# ioshield.net
KiCad netlist of a schematic drawn in EAGLE
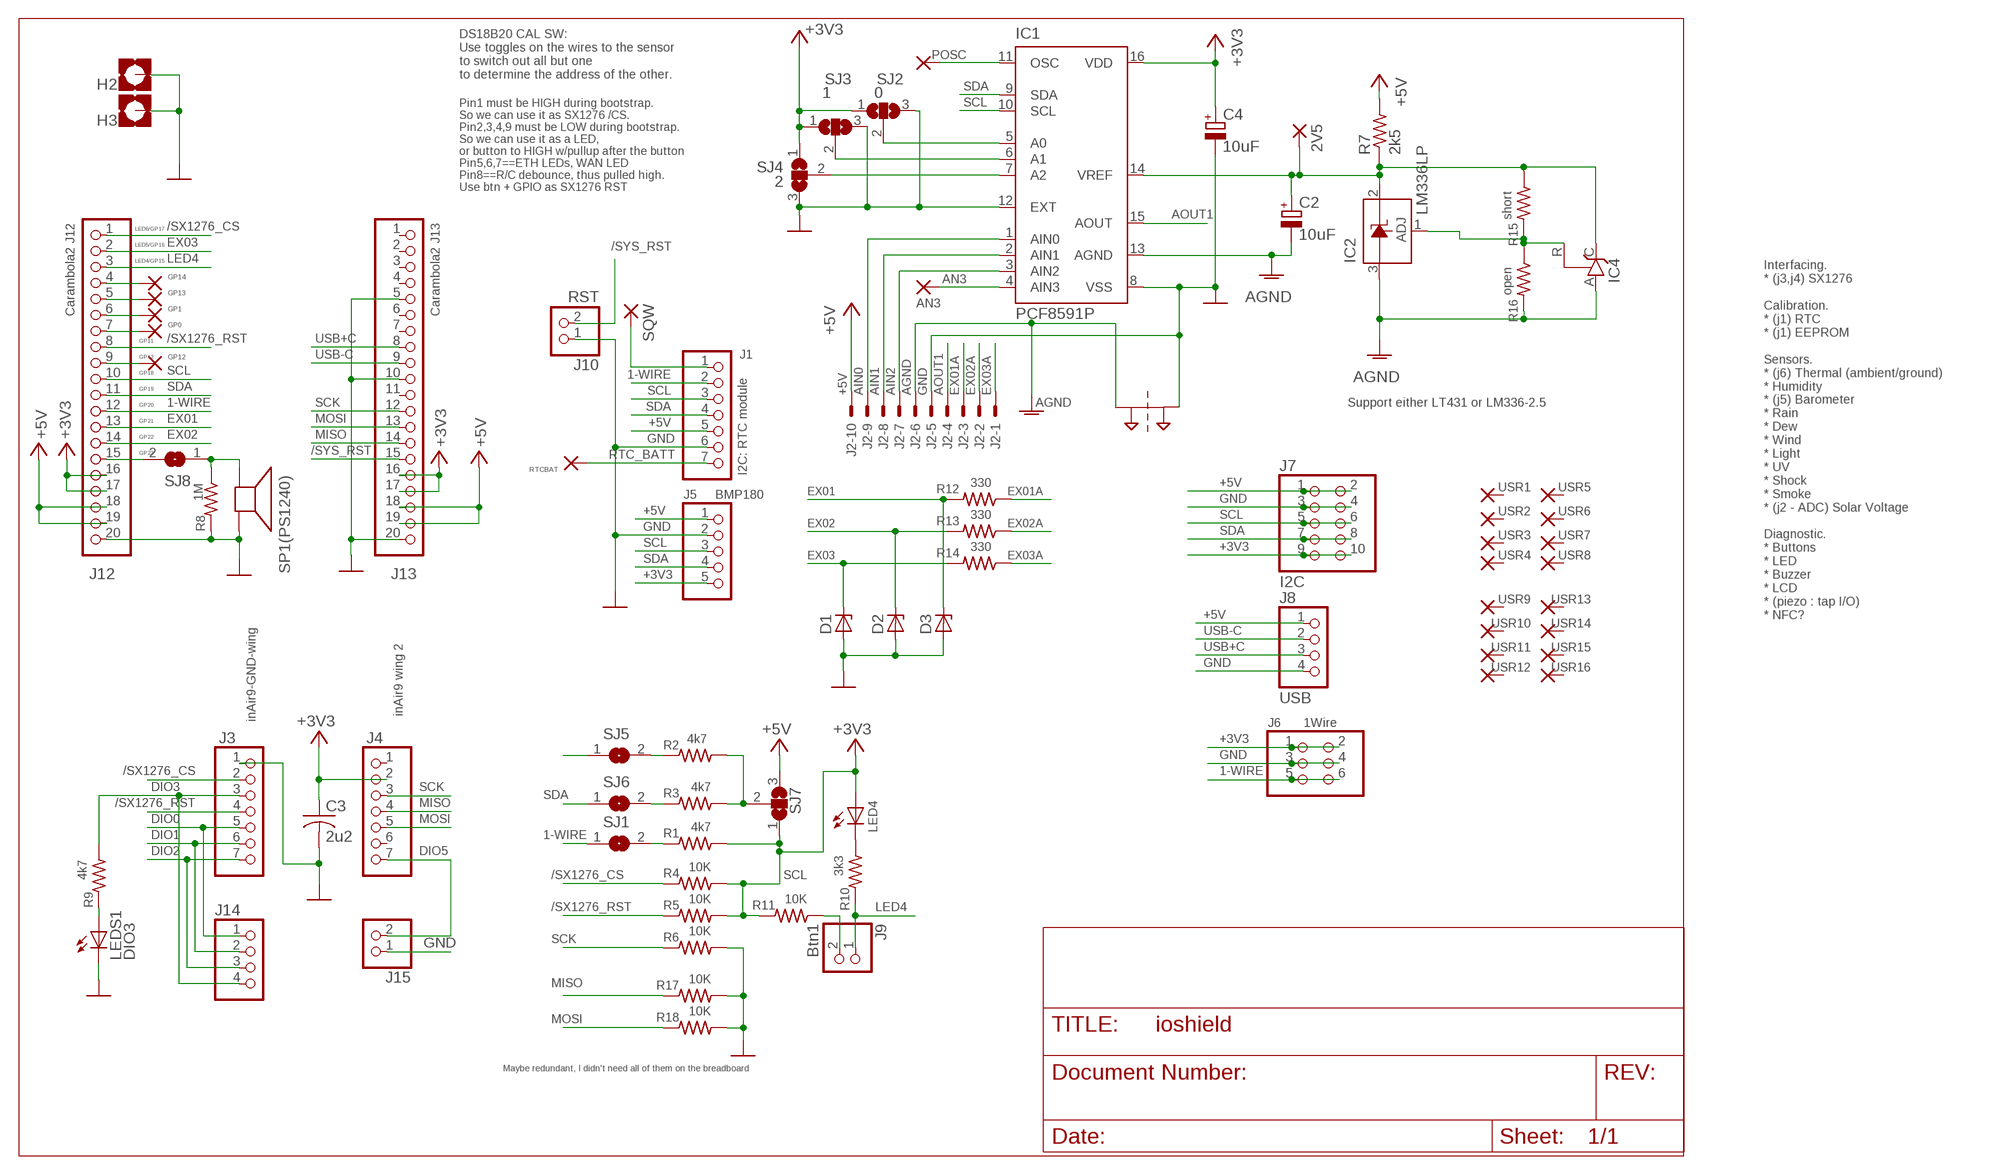
[diagram p0: schematic, sheet 1]

(export (version "E")
  (design (tool "Eeschema 10.0.6"))
  (components
    (comp (ref "2V5")
      (value "2,54/0,8")
      (footprint "eagle-import:2,54_0,8")
      (libsource (lib "eagle-import") (part "2,54/0,8"))
    )
    (comp (ref "AN3")
      (value "AN3")
      (footprint "eagle-import:2,54_0,8")
      (libsource (lib "eagle-import") (part "2,54/0,8"))
    )
    (comp (ref "C2")
      (value "10uF")
      (footprint "eagle-import:E2,5-5")
      (libsource (lib "eagle-import") (part "CPOL-EUE2.5-5"))
    )
    (comp (ref "C3")
      (value "2u2")
      (footprint "eagle-import:C1206")
      (libsource (lib "eagle-import") (part "C-USC1206"))
    )
    (comp (ref "C4")
      (value "10uF")
      (footprint "eagle-import:E2,5-5")
      (libsource (lib "eagle-import") (part "CPOL-EUE2.5-5"))
    )
    (comp (ref "D1")
      (value "ZENER-DIODEZD-2.5")
      (footprint "eagle-import:ZDIO-2.5")
      (libsource (lib "eagle-import") (part "ZENER-DIODEZD-2.5"))
    )
    (comp (ref "D2")
      (value "ZENER-DIODEZD-2.5")
      (footprint "eagle-import:ZDIO-2.5")
      (libsource (lib "eagle-import") (part "ZENER-DIODEZD-2.5"))
    )
    (comp (ref "D3")
      (value "ZENER-DIODEZD-2.5")
      (footprint "eagle-import:ZDIO-2.5")
      (libsource (lib "eagle-import") (part "ZENER-DIODEZD-2.5"))
    )
    (comp (ref "GP0")
      (value "2,54/0,8")
      (footprint "eagle-import:2,54_0,8")
      (libsource (lib "eagle-import") (part "2,54/0,8"))
    )
    (comp (ref "GP1")
      (value "2,54/0,8")
      (footprint "eagle-import:2,54_0,8")
      (libsource (lib "eagle-import") (part "2,54/0,8"))
    )
    (comp (ref "GP12")
      (value "2,54/0,8")
      (footprint "eagle-import:2,54_0,8")
      (libsource (lib "eagle-import") (part "2,54/0,8"))
    )
    (comp (ref "GP13")
      (value "2,54/0,8")
      (footprint "eagle-import:2,54_0,8")
      (libsource (lib "eagle-import") (part "2,54/0,8"))
    )
    (comp (ref "GP14")
      (value "2,54/0,8")
      (footprint "eagle-import:2,54_0,8")
      (libsource (lib "eagle-import") (part "2,54/0,8"))
    )
    (comp (ref "H2")
      (value "MOUNT-PAD-SQUARE3.2")
      (footprint "eagle-import:3,2-PAD-SQUARE")
      (libsource (lib "eagle-import") (part "MOUNT-PAD-SQUARE3.2"))
    )
    (comp (ref "H3")
      (value "MOUNT-PAD-SQUARE3.2")
      (footprint "eagle-import:3,2-PAD-SQUARE")
      (libsource (lib "eagle-import") (part "MOUNT-PAD-SQUARE3.2"))
    )
    (comp (ref "IC1")
      (value "PCF8591P")
      (footprint "eagle-import:DIL16")
      (fields (field (name "MF") "FARNELL"))
      (libsource (lib "eagle-import") (part "PCF8591P"))
    )
    (comp (ref "IC2")
      (value "LM336LP")
      (footprint "eagle-import:TO92")
      (libsource (lib "eagle-import") (part "LM336LP"))
    )
    (comp (ref "IC4")
      (value "TL431CLP")
      (footprint "eagle-import:TO92-CLP")
      (libsource (lib "eagle-import") (part "TL431CLP"))
    )
    (comp (ref "J1")
      (value "I2C: RTC module")
      (footprint "eagle-import:1X07")
      (libsource (lib "eagle-import") (part "PINHD-1X7"))
    )
    (comp (ref "J2")
      (value "22-23-2101")
      (footprint "eagle-import:22-23-2101")
      (fields (field (name "MF") "MOLEX") (field (name "MPN") "Screw Terminal"))
      (libsource (lib "eagle-import") (part "22-23-2101"))
    )
    (comp (ref "J3")
      (value "inAir9-GND-wing")
      (footprint "eagle-import:1X07")
      (libsource (lib "eagle-import") (part "PINHD-1X7"))
    )
    (comp (ref "J4")
      (value "inAir9 wing 2")
      (footprint "eagle-import:1X07")
      (libsource (lib "eagle-import") (part "PINHD-1X7"))
    )
    (comp (ref "J5")
      (value "BMP180")
      (footprint "eagle-import:1X05")
      (libsource (lib "eagle-import") (part "PINHD-1X5"))
    )
    (comp (ref "J6")
      (value "1Wire")
      (footprint "eagle-import:2X03")
      (libsource (lib "eagle-import") (part "PINHD-2X3"))
    )
    (comp (ref "J7")
      (value "I2C")
      (footprint "eagle-import:2X05")
      (libsource (lib "eagle-import") (part "PINHD-2X5"))
    )
    (comp (ref "J8")
      (value "USB")
      (footprint "eagle-import:1X04")
      (libsource (lib "eagle-import") (part "PINHD-1X4"))
    )
    (comp (ref "J9")
      (value "Btn1")
      (footprint "eagle-import:1X02")
      (libsource (lib "eagle-import") (part "PINHD-1X2"))
    )
    (comp (ref "J10")
      (value "RST")
      (footprint "eagle-import:1X02")
      (libsource (lib "eagle-import") (part "PINHD-1X2"))
    )
    (comp (ref "J12")
      (value "Carambola2 J12")
      (footprint "eagle-import:1X20")
      (libsource (lib "eagle-import") (part "PINHD-1X20"))
    )
    (comp (ref "J13")
      (value "Carambola2 J13")
      (footprint "eagle-import:1X20")
      (libsource (lib "eagle-import") (part "PINHD-1X20"))
    )
    (comp (ref "J14")
      (value "PINHD-1X4")
      (footprint "eagle-import:1X04")
      (libsource (lib "eagle-import") (part "PINHD-1X4"))
    )
    (comp (ref "J15")
      (value "PINHD-1X2")
      (footprint "eagle-import:1X02")
      (libsource (lib "eagle-import") (part "PINHD-1X2"))
    )
    (comp (ref "LED4")
      (value "LED3MM")
      (footprint "eagle-import:LED3MM")
      (libsource (lib "eagle-import") (part "LED3MM"))
    )
    (comp (ref "LEDS1")
      (value "DIO3")
      (footprint "eagle-import:LED3MM")
      (libsource (lib "eagle-import") (part "LED3MM"))
    )
    (comp (ref "POSC")
      (value "2,54/0,8")
      (footprint "eagle-import:2,54_0,8")
      (libsource (lib "eagle-import") (part "2,54/0,8"))
    )
    (comp (ref "PT1")
      (value "2PT_GND_TIE")
      (footprint "eagle-import:2PT_GND_TIE")
      (libsource (lib "eagle-import") (part "2PT_GND_TIE"))
    )
    (comp (ref "R1")
      (value "4k7")
      (footprint "eagle-import:M1206")
      (libsource (lib "eagle-import") (part "R-US_M1206"))
    )
    (comp (ref "R2")
      (value "4k7")
      (footprint "eagle-import:M1206")
      (libsource (lib "eagle-import") (part "R-US_M1206"))
    )
    (comp (ref "R3")
      (value "4k7")
      (footprint "eagle-import:M1206")
      (libsource (lib "eagle-import") (part "R-US_M1206"))
    )
    (comp (ref "R4")
      (value "10K")
      (footprint "eagle-import:M1206")
      (libsource (lib "eagle-import") (part "R-US_M1206"))
    )
    (comp (ref "R5")
      (value "10K")
      (footprint "eagle-import:M1206")
      (libsource (lib "eagle-import") (part "R-US_M1206"))
    )
    (comp (ref "R6")
      (value "10K")
      (footprint "eagle-import:M1206")
      (libsource (lib "eagle-import") (part "R-US_M1206"))
    )
    (comp (ref "R7")
      (value "2k5")
      (footprint "eagle-import:M1206")
      (libsource (lib "eagle-import") (part "R-US_M1206"))
    )
    (comp (ref "R8")
      (value "1M")
      (footprint "eagle-import:M1206")
      (libsource (lib "eagle-import") (part "R-US_M1206"))
    )
    (comp (ref "R9")
      (value "4k7")
      (footprint "eagle-import:M1206")
      (libsource (lib "eagle-import") (part "R-US_M1206"))
    )
    (comp (ref "R10")
      (value "3k3")
      (footprint "eagle-import:M1206")
      (libsource (lib "eagle-import") (part "R-US_M1206"))
    )
    (comp (ref "R11")
      (value "10K")
      (footprint "eagle-import:M1206")
      (libsource (lib "eagle-import") (part "R-US_M1206"))
    )
    (comp (ref "R12")
      (value "330")
      (footprint "eagle-import:M1206")
      (libsource (lib "eagle-import") (part "R-US_M1206"))
    )
    (comp (ref "R13")
      (value "330")
      (footprint "eagle-import:M1206")
      (libsource (lib "eagle-import") (part "R-US_M1206"))
    )
    (comp (ref "R14")
      (value "330")
      (footprint "eagle-import:M1206")
      (libsource (lib "eagle-import") (part "R-US_M1206"))
    )
    (comp (ref "R15")
      (value "short")
      (footprint "eagle-import:M1206")
      (libsource (lib "eagle-import") (part "R-US_M1206"))
    )
    (comp (ref "R16")
      (value "open")
      (footprint "eagle-import:M1206")
      (libsource (lib "eagle-import") (part "R-US_M1206"))
    )
    (comp (ref "R17")
      (value "10K")
      (footprint "eagle-import:M1206")
      (libsource (lib "eagle-import") (part "R-US_M1206"))
    )
    (comp (ref "R18")
      (value "10K")
      (footprint "eagle-import:M1206")
      (libsource (lib "eagle-import") (part "R-US_M1206"))
    )
    (comp (ref "RTCBAT")
      (value "2,54/0,8")
      (footprint "eagle-import:2,54_0,8")
      (libsource (lib "eagle-import") (part "2,54/0,8"))
    )
    (comp (ref "SJ1") (value "SJ") (footprint "eagle-import:SJ") (libsource (lib "eagle-import") (part "SJ")))
    (comp (ref "SJ2")
      (value "0")
      (footprint "eagle-import:SJ_2")
      (libsource (lib "eagle-import") (part "SJ2W"))
    )
    (comp (ref "SJ3")
      (value "1")
      (footprint "eagle-import:SJ_2")
      (libsource (lib "eagle-import") (part "SJ2W"))
    )
    (comp (ref "SJ4")
      (value "2")
      (footprint "eagle-import:SJ_2")
      (libsource (lib "eagle-import") (part "SJ2W"))
    )
    (comp (ref "SJ5") (value "SJ") (footprint "eagle-import:SJ") (libsource (lib "eagle-import") (part "SJ")))
    (comp (ref "SJ6") (value "SJ") (footprint "eagle-import:SJ") (libsource (lib "eagle-import") (part "SJ")))
    (comp (ref "SJ7")
      (value "SJ2W")
      (footprint "eagle-import:SJ_2")
      (libsource (lib "eagle-import") (part "SJ2W"))
    )
    (comp (ref "SJ8") (value "SJ") (footprint "eagle-import:SJ") (libsource (lib "eagle-import") (part "SJ")))
    (comp (ref "SP1(PS1240)")
      (value "SPEAKER/AL11P")
      (footprint "eagle-import:AL11P")
      (libsource (lib "eagle-import") (part "SPEAKER/AL11P"))
    )
    (comp (ref "SQW")
      (value "2,54/0,8")
      (footprint "eagle-import:2,54_0,8")
      (libsource (lib "eagle-import") (part "2,54/0,8"))
    )
    (comp (ref "USR1")
      (value "1,6/0,8")
      (footprint "eagle-import:1,6_0,8")
      (libsource (lib "eagle-import") (part "1,6/0,8"))
    )
    (comp (ref "USR2")
      (value "1,6/0,8")
      (footprint "eagle-import:1,6_0,8")
      (libsource (lib "eagle-import") (part "1,6/0,8"))
    )
    (comp (ref "USR3")
      (value "1,6/0,8")
      (footprint "eagle-import:1,6_0,8")
      (libsource (lib "eagle-import") (part "1,6/0,8"))
    )
    (comp (ref "USR4")
      (value "1,6/0,8")
      (footprint "eagle-import:1,6_0,8")
      (libsource (lib "eagle-import") (part "1,6/0,8"))
    )
    (comp (ref "USR5")
      (value "1,6/0,8")
      (footprint "eagle-import:1,6_0,8")
      (libsource (lib "eagle-import") (part "1,6/0,8"))
    )
    (comp (ref "USR6")
      (value "1,6/0,8")
      (footprint "eagle-import:1,6_0,8")
      (libsource (lib "eagle-import") (part "1,6/0,8"))
    )
    (comp (ref "USR7")
      (value "1,6/0,8")
      (footprint "eagle-import:1,6_0,8")
      (libsource (lib "eagle-import") (part "1,6/0,8"))
    )
    (comp (ref "USR8")
      (value "1,6/0,8")
      (footprint "eagle-import:1,6_0,8")
      (libsource (lib "eagle-import") (part "1,6/0,8"))
    )
    (comp (ref "USR9")
      (value "1,6/0,8")
      (footprint "eagle-import:1,6_0,8")
      (libsource (lib "eagle-import") (part "1,6/0,8"))
    )
    (comp (ref "USR10")
      (value "1,6/0,8")
      (footprint "eagle-import:1,6_0,8")
      (libsource (lib "eagle-import") (part "1,6/0,8"))
    )
    (comp (ref "USR11")
      (value "1,6/0,8")
      (footprint "eagle-import:1,6_0,8")
      (libsource (lib "eagle-import") (part "1,6/0,8"))
    )
    (comp (ref "USR12")
      (value "1,6/0,8")
      (footprint "eagle-import:1,6_0,8")
      (libsource (lib "eagle-import") (part "1,6/0,8"))
    )
    (comp (ref "USR13")
      (value "1,6/0,8")
      (footprint "eagle-import:1,6_0,8")
      (libsource (lib "eagle-import") (part "1,6/0,8"))
    )
    (comp (ref "USR14")
      (value "1,6/0,8")
      (footprint "eagle-import:1,6_0,8")
      (libsource (lib "eagle-import") (part "1,6/0,8"))
    )
    (comp (ref "USR15")
      (value "1,6/0,8")
      (footprint "eagle-import:1,6_0,8")
      (libsource (lib "eagle-import") (part "1,6/0,8"))
    )
    (comp (ref "USR16")
      (value "1,6/0,8")
      (footprint "eagle-import:1,6_0,8")
      (libsource (lib "eagle-import") (part "1,6/0,8"))
    )
  )
  (nets
    (net (code "1") (name "+3V3") (class "Default")
      (node (ref "C3") (pin "1") (pinfunction "1_1") (pintype "passive"))
      (node (ref "C4") (pin "+") (pinfunction "+_+") (pintype "passive"))
      (node (ref "IC1") (pin "16") (pinfunction "VDD_16") (pintype "power_in"))
      (node (ref "J12") (pin "16") (pinfunction "16_16") (pintype "passive"))
      (node (ref "J12") (pin "17") (pinfunction "17_17") (pintype "passive"))
      (node (ref "J13") (pin "16") (pinfunction "16_16") (pintype "passive"))
      (node (ref "J13") (pin "17") (pinfunction "17_17") (pintype "passive"))
      (node (ref "J4") (pin "2") (pinfunction "2_2") (pintype "passive"))
      (node (ref "J5") (pin "5") (pinfunction "5_5") (pintype "passive"))
      (node (ref "J6") (pin "1") (pinfunction "1_1") (pintype "passive"))
      (node (ref "J6") (pin "2") (pinfunction "2_2") (pintype "passive"))
      (node (ref "J7") (pin "10") (pinfunction "10_10") (pintype "passive"))
      (node (ref "J7") (pin "9") (pinfunction "9_9") (pintype "passive"))
      (node (ref "LED4") (pin "A") (pinfunction "A_A") (pintype "passive"))
      (node (ref "R1") (pin "1") (pinfunction "1_1") (pintype "passive"))
      (node (ref "R11") (pin "2") (pinfunction "2_2") (pintype "passive"))
      (node (ref "R4") (pin "1") (pinfunction "1_1") (pintype "passive"))
      (node (ref "R5") (pin "1") (pinfunction "1_1") (pintype "passive"))
      (node (ref "SJ2") (pin "1") (pinfunction "1_1") (pintype "passive"))
      (node (ref "SJ3") (pin "1") (pinfunction "1_1") (pintype "passive"))
      (node (ref "SJ4") (pin "1") (pinfunction "1_1") (pintype "passive"))
      (node (ref "SJ7") (pin "1") (pinfunction "1_1") (pintype "passive"))
    )
    (net (code "2") (name "+5V") (class "Default")
      (node (ref "J1") (pin "5") (pinfunction "5_5") (pintype "passive"))
      (node (ref "J12") (pin "18") (pinfunction "18_18") (pintype "passive"))
      (node (ref "J12") (pin "19") (pinfunction "19_19") (pintype "passive"))
      (node (ref "J13") (pin "18") (pinfunction "18_18") (pintype "passive"))
      (node (ref "J13") (pin "19") (pinfunction "19_19") (pintype "passive"))
      (node (ref "J2") (pin "10") (pinfunction "S_10") (pintype "passive"))
      (node (ref "J5") (pin "1") (pinfunction "1_1") (pintype "passive"))
      (node (ref "J7") (pin "1") (pinfunction "1_1") (pintype "passive"))
      (node (ref "J7") (pin "2") (pinfunction "2_2") (pintype "passive"))
      (node (ref "J8") (pin "1") (pinfunction "1_1") (pintype "passive"))
      (node (ref "R7") (pin "2") (pinfunction "2_2") (pintype "passive"))
      (node (ref "SJ7") (pin "3") (pinfunction "3_3") (pintype "passive"))
    )
    (net (code "3") (name "/1-WIRE") (class "Default")
      (node (ref "J1") (pin "2") (pinfunction "2_2") (pintype "passive"))
      (node (ref "J12") (pin "12") (pinfunction "12_12") (pintype "passive"))
      (node (ref "J6") (pin "5") (pinfunction "5_5") (pintype "passive"))
      (node (ref "J6") (pin "6") (pinfunction "6_6") (pintype "passive"))
      (node (ref "SJ1") (pin "1") (pinfunction "1_1") (pintype "passive"))
    )
    (net (code "4") (name "/AIN0") (class "Default")
      (node (ref "IC1") (pin "1") (pinfunction "AIN0_1") (pintype "input"))
      (node (ref "J2") (pin "9") (pinfunction "S_9") (pintype "passive"))
    )
    (net (code "5") (name "/AIN1") (class "Default")
      (node (ref "IC1") (pin "2") (pinfunction "AIN1_2") (pintype "input"))
      (node (ref "J2") (pin "8") (pinfunction "S_8") (pintype "passive"))
    )
    (net (code "6") (name "/AIN2") (class "Default")
      (node (ref "IC1") (pin "3") (pinfunction "AIN2_3") (pintype "input"))
      (node (ref "J2") (pin "7") (pinfunction "S_7") (pintype "passive"))
    )
    (net (code "7") (name "/AOUT1") (class "Default")
      (node (ref "IC1") (pin "15") (pinfunction "AOUT_15") (pintype "output"))
      (node (ref "J2") (pin "4") (pinfunction "S_4") (pintype "passive"))
    )
    (net (code "8") (name "/DIO0") (class "Default")
      (node (ref "J14") (pin "1") (pinfunction "1_1") (pintype "passive"))
      (node (ref "J3") (pin "5") (pinfunction "5_5") (pintype "passive"))
    )
    (net (code "9") (name "/DIO1") (class "Default")
      (node (ref "J14") (pin "2") (pinfunction "2_2") (pintype "passive"))
      (node (ref "J3") (pin "6") (pinfunction "6_6") (pintype "passive"))
    )
    (net (code "10") (name "/DIO2") (class "Default")
      (node (ref "J14") (pin "3") (pinfunction "3_3") (pintype "passive"))
      (node (ref "J3") (pin "7") (pinfunction "7_7") (pintype "passive"))
    )
    (net (code "11") (name "/DIO3") (class "Default")
      (node (ref "J14") (pin "4") (pinfunction "4_4") (pintype "passive"))
      (node (ref "J3") (pin "3") (pinfunction "3_3") (pintype "passive"))
      (node (ref "R9") (pin "1") (pinfunction "1_1") (pintype "passive"))
    )
    (net (code "12") (name "/DIO5") (class "Default")
      (node (ref "J15") (pin "2") (pinfunction "2_2") (pintype "passive"))
      (node (ref "J4") (pin "7") (pinfunction "7_7") (pintype "passive"))
    )
    (net (code "13") (name "/EX01") (class "Default")
      (node (ref "D3") (pin "C") (pinfunction "C_C") (pintype "passive"))
      (node (ref "J12") (pin "13") (pinfunction "13_13") (pintype "passive"))
      (node (ref "R12") (pin "2") (pinfunction "2_2") (pintype "passive"))
    )
    (net (code "14") (name "/EX01A") (class "Default")
      (node (ref "J2") (pin "3") (pinfunction "S_3") (pintype "passive"))
      (node (ref "R12") (pin "1") (pinfunction "1_1") (pintype "passive"))
    )
    (net (code "15") (name "/EX02") (class "Default")
      (node (ref "D2") (pin "C") (pinfunction "C_C") (pintype "passive"))
      (node (ref "J12") (pin "14") (pinfunction "14_14") (pintype "passive"))
      (node (ref "R13") (pin "2") (pinfunction "2_2") (pintype "passive"))
    )
    (net (code "16") (name "/EX02A") (class "Default")
      (node (ref "J2") (pin "2") (pinfunction "S_2") (pintype "passive"))
      (node (ref "R13") (pin "1") (pinfunction "1_1") (pintype "passive"))
    )
    (net (code "17") (name "/EX03") (class "Default")
      (node (ref "D1") (pin "C") (pinfunction "C_C") (pintype "passive"))
      (node (ref "J12") (pin "2") (pinfunction "2_2") (pintype "passive"))
      (node (ref "R14") (pin "2") (pinfunction "2_2") (pintype "passive"))
    )
    (net (code "18") (name "/EX03A") (class "Default")
      (node (ref "J2") (pin "1") (pinfunction "S_1") (pintype "passive"))
      (node (ref "R14") (pin "1") (pinfunction "1_1") (pintype "passive"))
    )
    (net (code "19") (name "/LED4") (class "Default")
      (node (ref "J12") (pin "3") (pinfunction "3_3") (pintype "passive"))
      (node (ref "J9") (pin "1") (pinfunction "1_1") (pintype "passive"))
      (node (ref "R10") (pin "2") (pinfunction "2_2") (pintype "passive"))
    )
    (net (code "20") (name "/MISO") (class "Default")
      (node (ref "J13") (pin "14") (pinfunction "14_14") (pintype "passive"))
      (node (ref "J4") (pin "4") (pinfunction "4_4") (pintype "passive"))
      (node (ref "R17") (pin "2") (pinfunction "2_2") (pintype "passive"))
    )
    (net (code "21") (name "/MOSI") (class "Default")
      (node (ref "J13") (pin "13") (pinfunction "13_13") (pintype "passive"))
      (node (ref "J4") (pin "5") (pinfunction "5_5") (pintype "passive"))
      (node (ref "R18") (pin "2") (pinfunction "2_2") (pintype "passive"))
    )
    (net (code "22") (name "/RTC_BATT") (class "Default")
      (node (ref "J1") (pin "7") (pinfunction "7_7") (pintype "passive"))
      (node (ref "RTCBAT") (pin "1") (pinfunction "P_1") (pintype "passive"))
    )
    (net (code "23") (name "/SCK") (class "Default")
      (node (ref "J13") (pin "12") (pinfunction "12_12") (pintype "passive"))
      (node (ref "J4") (pin "3") (pinfunction "3_3") (pintype "passive"))
      (node (ref "R6") (pin "2") (pinfunction "2_2") (pintype "passive"))
    )
    (net (code "24") (name "/SCL") (class "Default")
      (node (ref "IC1") (pin "10") (pinfunction "SCL_10") (pintype "input"))
      (node (ref "J1") (pin "3") (pinfunction "3_3") (pintype "passive"))
      (node (ref "J12") (pin "10") (pinfunction "10_10") (pintype "passive"))
      (node (ref "J5") (pin "3") (pinfunction "3_3") (pintype "passive"))
      (node (ref "J7") (pin "5") (pinfunction "5_5") (pintype "passive"))
      (node (ref "J7") (pin "6") (pinfunction "6_6") (pintype "passive"))
      (node (ref "SJ5") (pin "1") (pinfunction "1_1") (pintype "passive"))
    )
    (net (code "25") (name "/SDA") (class "Default")
      (node (ref "IC1") (pin "9") (pinfunction "SDA_9") (pintype "bidirectional"))
      (node (ref "J1") (pin "4") (pinfunction "4_4") (pintype "passive"))
      (node (ref "J12") (pin "11") (pinfunction "11_11") (pintype "passive"))
      (node (ref "J5") (pin "4") (pinfunction "4_4") (pintype "passive"))
      (node (ref "J7") (pin "7") (pinfunction "7_7") (pintype "passive"))
      (node (ref "J7") (pin "8") (pinfunction "8_8") (pintype "passive"))
      (node (ref "SJ6") (pin "1") (pinfunction "1_1") (pintype "passive"))
    )
    (net (code "26") (name "/USB+C") (class "Default")
      (node (ref "J13") (pin "8") (pinfunction "8_8") (pintype "passive"))
      (node (ref "J8") (pin "3") (pinfunction "3_3") (pintype "passive"))
    )
    (net (code "27") (name "/USB-C") (class "Default")
      (node (ref "J13") (pin "9") (pinfunction "9_9") (pintype "passive"))
      (node (ref "J8") (pin "2") (pinfunction "2_2") (pintype "passive"))
    )
    (net (code "28") (name "/{slash}SX1276_CS") (class "Default")
      (node (ref "J12") (pin "1") (pinfunction "1_1") (pintype "passive"))
      (node (ref "J3") (pin "2") (pinfunction "2_2") (pintype "passive"))
      (node (ref "R4") (pin "2") (pinfunction "2_2") (pintype "passive"))
    )
    (net (code "29") (name "/{slash}SX1276_RST") (class "Default")
      (node (ref "J12") (pin "8") (pinfunction "8_8") (pintype "passive"))
      (node (ref "J3") (pin "4") (pinfunction "4_4") (pintype "passive"))
      (node (ref "R5") (pin "2") (pinfunction "2_2") (pintype "passive"))
    )
    (net (code "30") (name "/{slash}SYS_RST") (class "Default")
      (node (ref "J10") (pin "2") (pinfunction "2_2") (pintype "passive"))
      (node (ref "J13") (pin "15") (pinfunction "15_15") (pintype "passive"))
    )
    (net (code "31") (name "AGND") (class "Default")
      (node (ref "C2") (pin "-") (pinfunction "-_-") (pintype "passive"))
      (node (ref "IC1") (pin "13") (pinfunction "AGND_13") (pintype "power_in"))
      (node (ref "IC2") (pin "3") (pinfunction "A_3") (pintype "input"))
      (node (ref "IC4") (pin "A") (pinfunction "A_A") (pintype "passive"))
      (node (ref "J2") (pin "6") (pinfunction "S_6") (pintype "passive"))
      (node (ref "PT1") (pin "P$1") (pinfunction "P$1_P$1") (pintype "bidirectional"))
      (node (ref "R16") (pin "2") (pinfunction "2_2") (pintype "passive"))
    )
    (net (code "32") (name "GND") (class "Default")
      (node (ref "C3") (pin "2") (pinfunction "2_2") (pintype "passive"))
      (node (ref "C4") (pin "-") (pinfunction "-_-") (pintype "passive"))
      (node (ref "D1") (pin "A") (pinfunction "A_A") (pintype "passive"))
      (node (ref "D2") (pin "A") (pinfunction "A_A") (pintype "passive"))
      (node (ref "D3") (pin "A") (pinfunction "A_A") (pintype "passive"))
      (node (ref "H2") (pin "B3,2") (pinfunction "MOUNT_B3,2") (pintype "passive"))
      (node (ref "H3") (pin "B3,2") (pinfunction "MOUNT_B3,2") (pintype "passive"))
      (node (ref "IC1") (pin "12") (pinfunction "EXT_12") (pintype "input"))
      (node (ref "IC1") (pin "8") (pinfunction "VSS_8") (pintype "power_in"))
      (node (ref "J1") (pin "6") (pinfunction "6_6") (pintype "passive"))
      (node (ref "J10") (pin "1") (pinfunction "1_1") (pintype "passive"))
      (node (ref "J12") (pin "20") (pinfunction "20_20") (pintype "passive"))
      (node (ref "J13") (pin "10") (pinfunction "10_10") (pintype "passive"))
      (node (ref "J13") (pin "20") (pinfunction "20_20") (pintype "passive"))
      (node (ref "J13") (pin "5") (pinfunction "5_5") (pintype "passive"))
      (node (ref "J15") (pin "1") (pinfunction "1_1") (pintype "passive"))
      (node (ref "J2") (pin "5") (pinfunction "S_5") (pintype "passive"))
      (node (ref "J3") (pin "1") (pinfunction "1_1") (pintype "passive"))
      (node (ref "J5") (pin "2") (pinfunction "2_2") (pintype "passive"))
      (node (ref "J6") (pin "3") (pinfunction "3_3") (pintype "passive"))
      (node (ref "J6") (pin "4") (pinfunction "4_4") (pintype "passive"))
      (node (ref "J7") (pin "3") (pinfunction "3_3") (pintype "passive"))
      (node (ref "J7") (pin "4") (pinfunction "4_4") (pintype "passive"))
      (node (ref "J8") (pin "4") (pinfunction "4_4") (pintype "passive"))
      (node (ref "LEDS1") (pin "K") (pinfunction "C_K") (pintype "passive"))
      (node (ref "PT1") (pin "P$2") (pinfunction "P$2_P$2") (pintype "bidirectional"))
      (node (ref "R17") (pin "1") (pinfunction "1_1") (pintype "passive"))
      (node (ref "R18") (pin "1") (pinfunction "1_1") (pintype "passive"))
      (node (ref "R6") (pin "1") (pinfunction "1_1") (pintype "passive"))
      (node (ref "R8") (pin "2") (pinfunction "2_2") (pintype "passive"))
      (node (ref "SJ2") (pin "3") (pinfunction "3_3") (pintype "passive"))
      (node (ref "SJ3") (pin "3") (pinfunction "3_3") (pintype "passive"))
      (node (ref "SJ4") (pin "3") (pinfunction "3_3") (pintype "passive"))
      (node (ref "SP1(PS1240)") (pin "-") (pinfunction "-_-") (pintype "passive"))
    )
    (net (code "33") (name "Net-(2V5-P)") (class "Default")
      (node (ref "2V5") (pin "1") (pinfunction "P_1") (pintype "passive"))
      (node (ref "C2") (pin "+") (pinfunction "+_+") (pintype "passive"))
      (node (ref "IC1") (pin "14") (pinfunction "VREF_14") (pintype "input"))
      (node (ref "IC2") (pin "2") (pinfunction "C_2") (pintype "passive"))
      (node (ref "IC4") (pin "C") (pinfunction "C_C") (pintype "passive"))
      (node (ref "R15") (pin "1") (pinfunction "1_1") (pintype "passive"))
      (node (ref "R7") (pin "1") (pinfunction "1_1") (pintype "passive"))
    )
    (net (code "34") (name "Net-(AN3-P)") (class "Default")
      (node (ref "AN3") (pin "1") (pinfunction "P_1") (pintype "passive"))
      (node (ref "IC1") (pin "4") (pinfunction "AIN3_4") (pintype "input"))
    )
    (net (code "35") (name "Net-(GP0-P)") (class "Default")
      (node (ref "GP0") (pin "1") (pinfunction "P_1") (pintype "passive"))
      (node (ref "J12") (pin "7") (pinfunction "7_7") (pintype "passive"))
    )
    (net (code "36") (name "Net-(GP1-P)") (class "Default")
      (node (ref "GP1") (pin "1") (pinfunction "P_1") (pintype "passive"))
      (node (ref "J12") (pin "6") (pinfunction "6_6") (pintype "passive"))
    )
    (net (code "37") (name "Net-(GP12-P)") (class "Default")
      (node (ref "GP12") (pin "1") (pinfunction "P_1") (pintype "passive"))
      (node (ref "J12") (pin "9") (pinfunction "9_9") (pintype "passive"))
    )
    (net (code "38") (name "Net-(GP13-P)") (class "Default")
      (node (ref "GP13") (pin "1") (pinfunction "P_1") (pintype "passive"))
      (node (ref "J12") (pin "5") (pinfunction "5_5") (pintype "passive"))
    )
    (net (code "39") (name "Net-(GP14-P)") (class "Default")
      (node (ref "GP14") (pin "1") (pinfunction "P_1") (pintype "passive"))
      (node (ref "J12") (pin "4") (pinfunction "4_4") (pintype "passive"))
    )
    (net (code "40") (name "Net-(IC1-A0)") (class "Default")
      (node (ref "IC1") (pin "5") (pinfunction "A0_5") (pintype "input"))
      (node (ref "SJ2") (pin "2") (pinfunction "2_2") (pintype "passive"))
    )
    (net (code "41") (name "Net-(IC1-A1)") (class "Default")
      (node (ref "IC1") (pin "6") (pinfunction "A1_6") (pintype "input"))
      (node (ref "SJ3") (pin "2") (pinfunction "2_2") (pintype "passive"))
    )
    (net (code "42") (name "Net-(IC1-A2)") (class "Default")
      (node (ref "IC1") (pin "7") (pinfunction "A2_7") (pintype "input"))
      (node (ref "SJ4") (pin "2") (pinfunction "2_2") (pintype "passive"))
    )
    (net (code "43") (name "Net-(IC1-OSC)") (class "Default")
      (node (ref "IC1") (pin "11") (pinfunction "OSC_11") (pintype "input"))
      (node (ref "POSC") (pin "1") (pinfunction "P_1") (pintype "passive"))
    )
    (net (code "44") (name "Net-(IC2-ADJ)") (class "Default")
      (node (ref "IC2") (pin "1") (pinfunction "ADJ_1") (pintype "input"))
      (node (ref "IC4") (pin "R") (pinfunction "R_R") (pintype "passive"))
      (node (ref "R15") (pin "2") (pinfunction "2_2") (pintype "passive"))
      (node (ref "R16") (pin "1") (pinfunction "1_1") (pintype "passive"))
    )
    (net (code "45") (name "Net-(J9-Pad2)") (class "Default")
      (node (ref "J9") (pin "2") (pinfunction "2_2") (pintype "passive"))
      (node (ref "R11") (pin "1") (pinfunction "1_1") (pintype "passive"))
    )
    (net (code "46") (name "Net-(J12-Pad15)") (class "Default")
      (node (ref "J12") (pin "15") (pinfunction "15_15") (pintype "passive"))
      (node (ref "SJ8") (pin "2") (pinfunction "2_2") (pintype "passive"))
    )
    (net (code "47") (name "Net-(LED4-C)") (class "Default")
      (node (ref "LED4") (pin "K") (pinfunction "C_K") (pintype "passive"))
      (node (ref "R10") (pin "1") (pinfunction "1_1") (pintype "passive"))
    )
    (net (code "48") (name "Net-(LEDS1-PadA)") (class "Default")
      (node (ref "LEDS1") (pin "A") (pinfunction "A_A") (pintype "passive"))
      (node (ref "R9") (pin "2") (pinfunction "2_2") (pintype "passive"))
    )
    (net (code "49") (name "Net-(R1-Pad2)") (class "Default")
      (node (ref "R1") (pin "2") (pinfunction "2_2") (pintype "passive"))
      (node (ref "SJ1") (pin "2") (pinfunction "2_2") (pintype "passive"))
    )
    (net (code "50") (name "Net-(R2-Pad1)") (class "Default")
      (node (ref "R2") (pin "1") (pinfunction "1_1") (pintype "passive"))
      (node (ref "R3") (pin "1") (pinfunction "1_1") (pintype "passive"))
      (node (ref "SJ7") (pin "2") (pinfunction "2_2") (pintype "passive"))
    )
    (net (code "51") (name "Net-(R2-Pad2)") (class "Default")
      (node (ref "R2") (pin "2") (pinfunction "2_2") (pintype "passive"))
      (node (ref "SJ5") (pin "2") (pinfunction "2_2") (pintype "passive"))
    )
    (net (code "52") (name "Net-(R3-Pad2)") (class "Default")
      (node (ref "R3") (pin "2") (pinfunction "2_2") (pintype "passive"))
      (node (ref "SJ6") (pin "2") (pinfunction "2_2") (pintype "passive"))
    )
    (net (code "53") (name "Net-(R8-Pad1)") (class "Default")
      (node (ref "R8") (pin "1") (pinfunction "1_1") (pintype "passive"))
      (node (ref "SJ8") (pin "1") (pinfunction "1_1") (pintype "passive"))
      (node (ref "SP1(PS1240)") (pin "+") (pinfunction "+_+") (pintype "passive"))
    )
    (net (code "54") (name "Net-(SQW-P)") (class "Default")
      (node (ref "J1") (pin "1") (pinfunction "1_1") (pintype "passive"))
      (node (ref "SQW") (pin "1") (pinfunction "P_1") (pintype "passive"))
    )
    (net (code "55") (name "unconnected-(J4-Pad1)") (class "Default")
      (node (ref "J4") (pin "1") (pinfunction "1_1") (pintype "passive"))
    )
    (net (code "56") (name "unconnected-(J4-Pad6)") (class "Default")
      (node (ref "J4") (pin "6") (pinfunction "6_6") (pintype "passive"))
    )
    (net (code "57") (name "unconnected-(J13-Pad1)") (class "Default")
      (node (ref "J13") (pin "1") (pinfunction "1_1") (pintype "passive"))
    )
    (net (code "58") (name "unconnected-(J13-Pad2)") (class "Default")
      (node (ref "J13") (pin "2") (pinfunction "2_2") (pintype "passive"))
    )
    (net (code "59") (name "unconnected-(J13-Pad3)") (class "Default")
      (node (ref "J13") (pin "3") (pinfunction "3_3") (pintype "passive"))
    )
    (net (code "60") (name "unconnected-(J13-Pad4)") (class "Default")
      (node (ref "J13") (pin "4") (pinfunction "4_4") (pintype "passive"))
    )
    (net (code "61") (name "unconnected-(J13-Pad6)") (class "Default")
      (node (ref "J13") (pin "6") (pinfunction "6_6") (pintype "passive"))
    )
    (net (code "62") (name "unconnected-(J13-Pad7)") (class "Default")
      (node (ref "J13") (pin "7") (pinfunction "7_7") (pintype "passive"))
    )
    (net (code "63") (name "unconnected-(J13-Pad11)") (class "Default")
      (node (ref "J13") (pin "11") (pinfunction "11_11") (pintype "passive"))
    )
    (net (code "64") (name "unconnected-(USR1-P-Pad1)") (class "Default")
      (node (ref "USR1") (pin "1") (pinfunction "P_1") (pintype "passive"))
    )
    (net (code "65") (name "unconnected-(USR2-P-Pad1)") (class "Default")
      (node (ref "USR2") (pin "1") (pinfunction "P_1") (pintype "passive"))
    )
    (net (code "66") (name "unconnected-(USR3-P-Pad1)") (class "Default")
      (node (ref "USR3") (pin "1") (pinfunction "P_1") (pintype "passive"))
    )
    (net (code "67") (name "unconnected-(USR4-P-Pad1)") (class "Default")
      (node (ref "USR4") (pin "1") (pinfunction "P_1") (pintype "passive"))
    )
    (net (code "68") (name "unconnected-(USR5-P-Pad1)") (class "Default")
      (node (ref "USR5") (pin "1") (pinfunction "P_1") (pintype "passive"))
    )
    (net (code "69") (name "unconnected-(USR6-P-Pad1)") (class "Default")
      (node (ref "USR6") (pin "1") (pinfunction "P_1") (pintype "passive"))
    )
    (net (code "70") (name "unconnected-(USR7-P-Pad1)") (class "Default")
      (node (ref "USR7") (pin "1") (pinfunction "P_1") (pintype "passive"))
    )
    (net (code "71") (name "unconnected-(USR8-P-Pad1)") (class "Default")
      (node (ref "USR8") (pin "1") (pinfunction "P_1") (pintype "passive"))
    )
    (net (code "72") (name "unconnected-(USR9-P-Pad1)") (class "Default")
      (node (ref "USR9") (pin "1") (pinfunction "P_1") (pintype "passive"))
    )
    (net (code "73") (name "unconnected-(USR10-P-Pad1)") (class "Default")
      (node (ref "USR10") (pin "1") (pinfunction "P_1") (pintype "passive"))
    )
    (net (code "74") (name "unconnected-(USR11-P-Pad1)") (class "Default")
      (node (ref "USR11") (pin "1") (pinfunction "P_1") (pintype "passive"))
    )
    (net (code "75") (name "unconnected-(USR12-P-Pad1)") (class "Default")
      (node (ref "USR12") (pin "1") (pinfunction "P_1") (pintype "passive"))
    )
    (net (code "76") (name "unconnected-(USR13-P-Pad1)") (class "Default")
      (node (ref "USR13") (pin "1") (pinfunction "P_1") (pintype "passive"))
    )
    (net (code "77") (name "unconnected-(USR14-P-Pad1)") (class "Default")
      (node (ref "USR14") (pin "1") (pinfunction "P_1") (pintype "passive"))
    )
    (net (code "78") (name "unconnected-(USR15-P-Pad1)") (class "Default")
      (node (ref "USR15") (pin "1") (pinfunction "P_1") (pintype "passive"))
    )
    (net (code "79") (name "unconnected-(USR16-P-Pad1)") (class "Default")
      (node (ref "USR16") (pin "1") (pinfunction "P_1") (pintype "passive"))
    )
  )
)
